# schematic.net
KiCad netlist of a schematic drawn in EAGLE
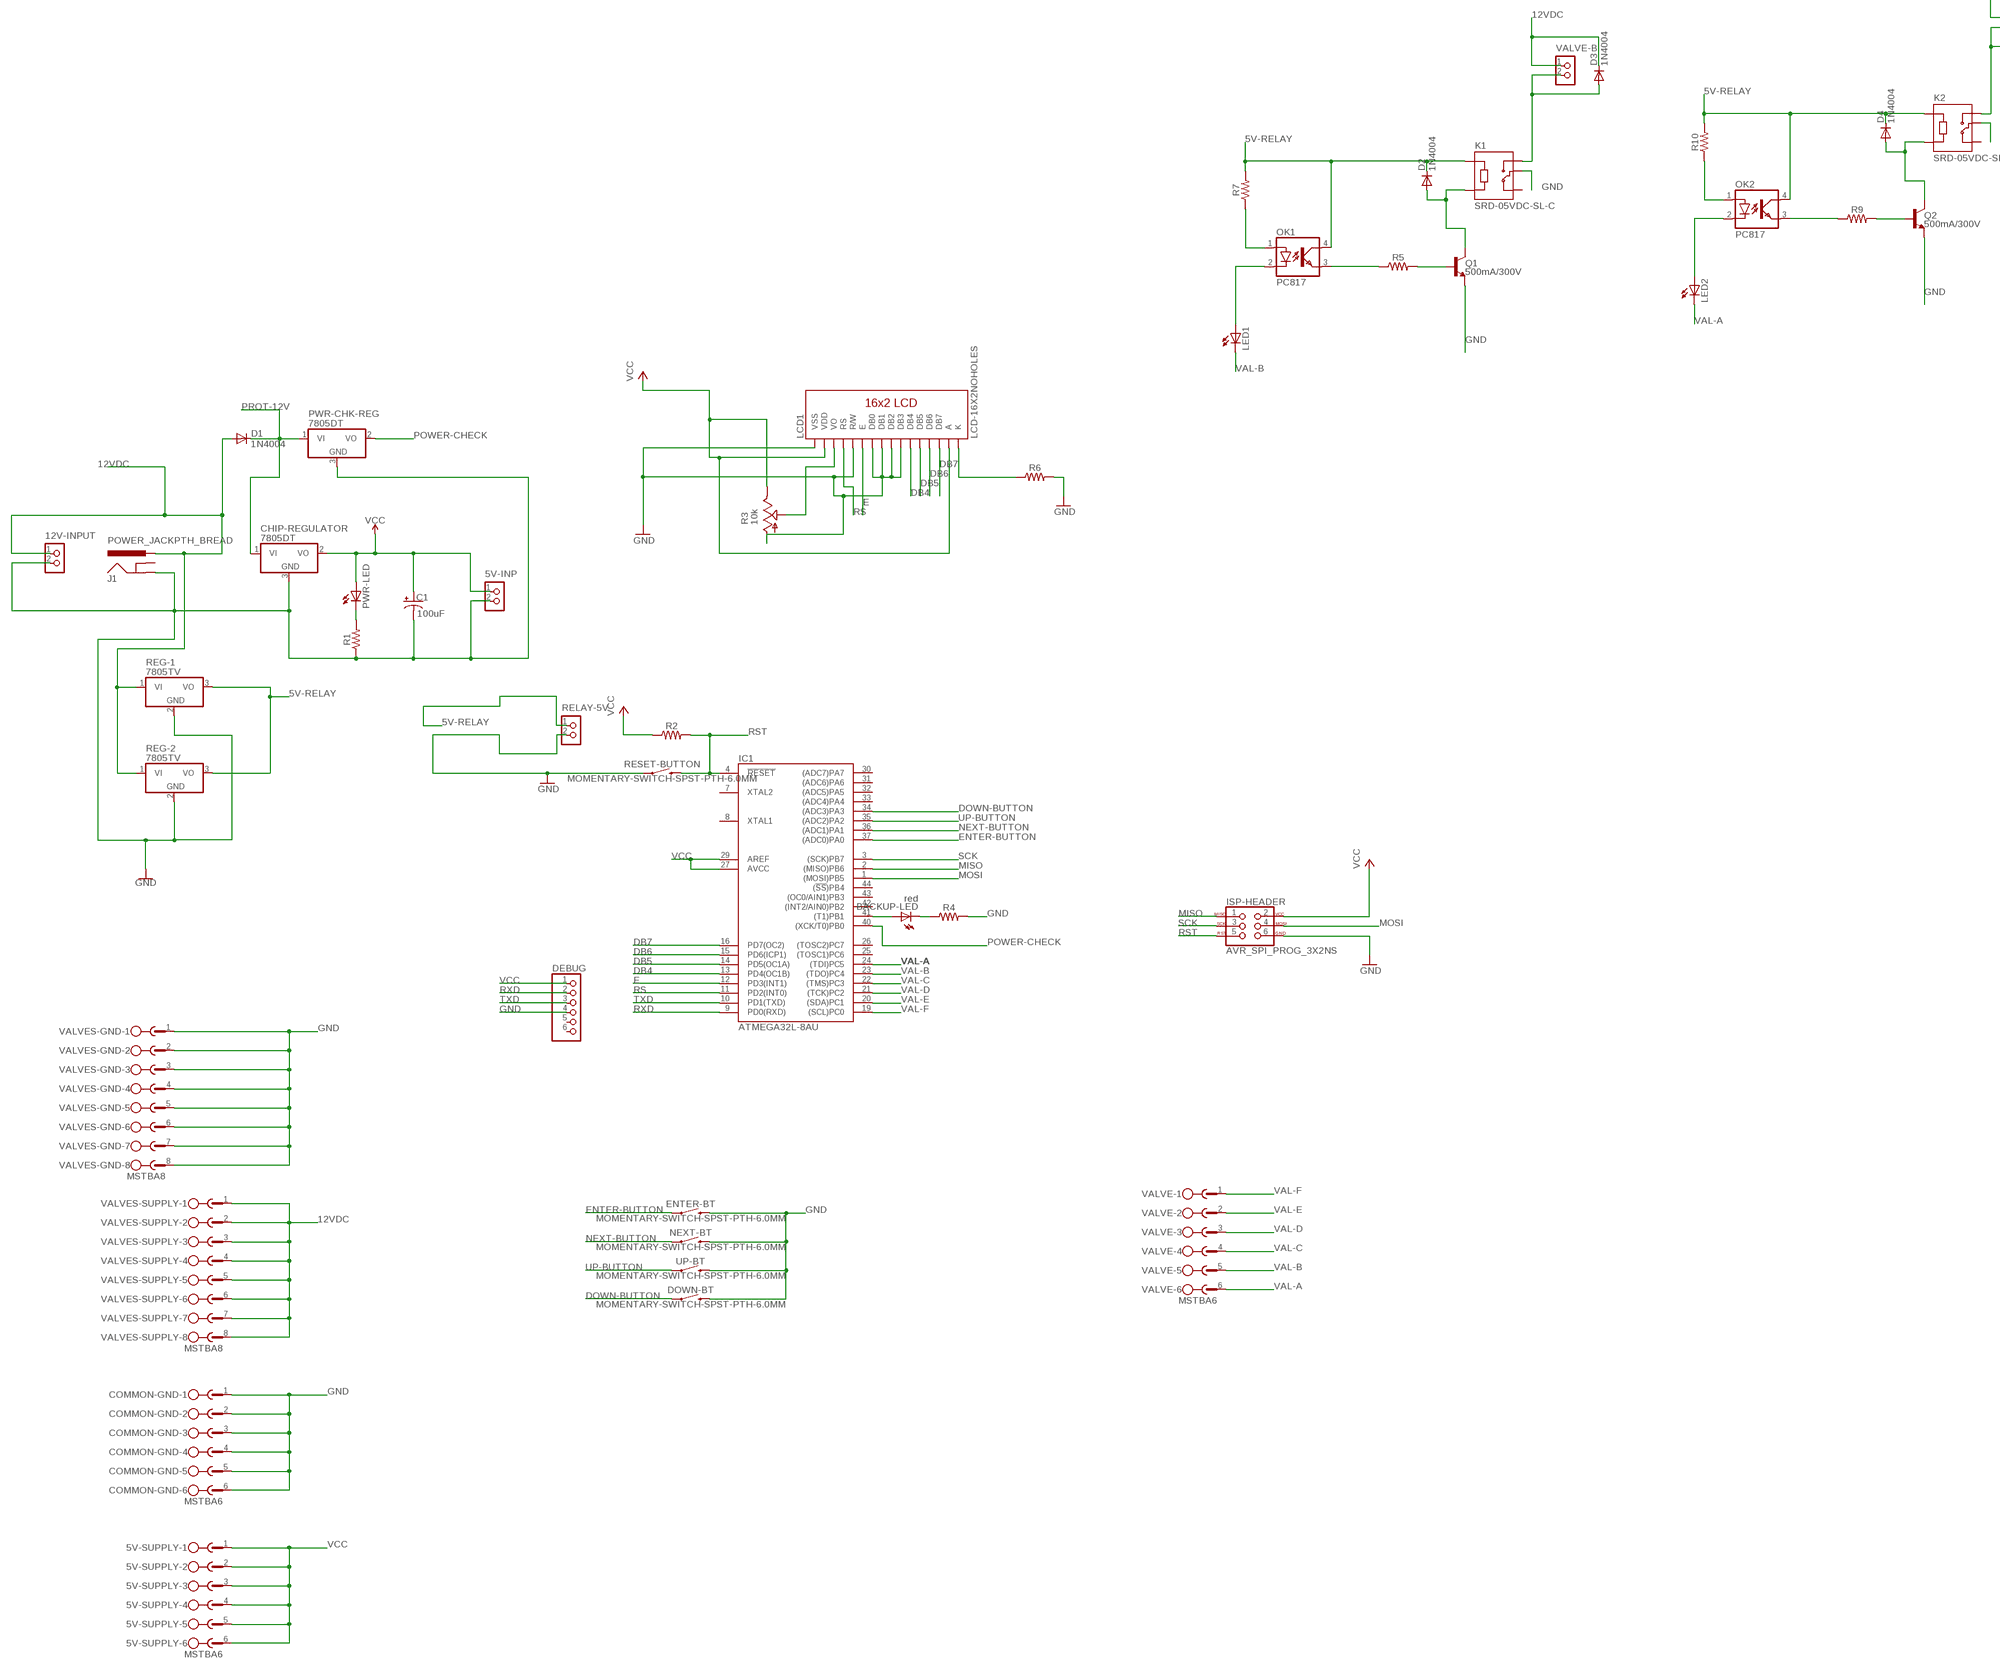
[diagram p0: schematic, sheet 1, part 1 of 2]
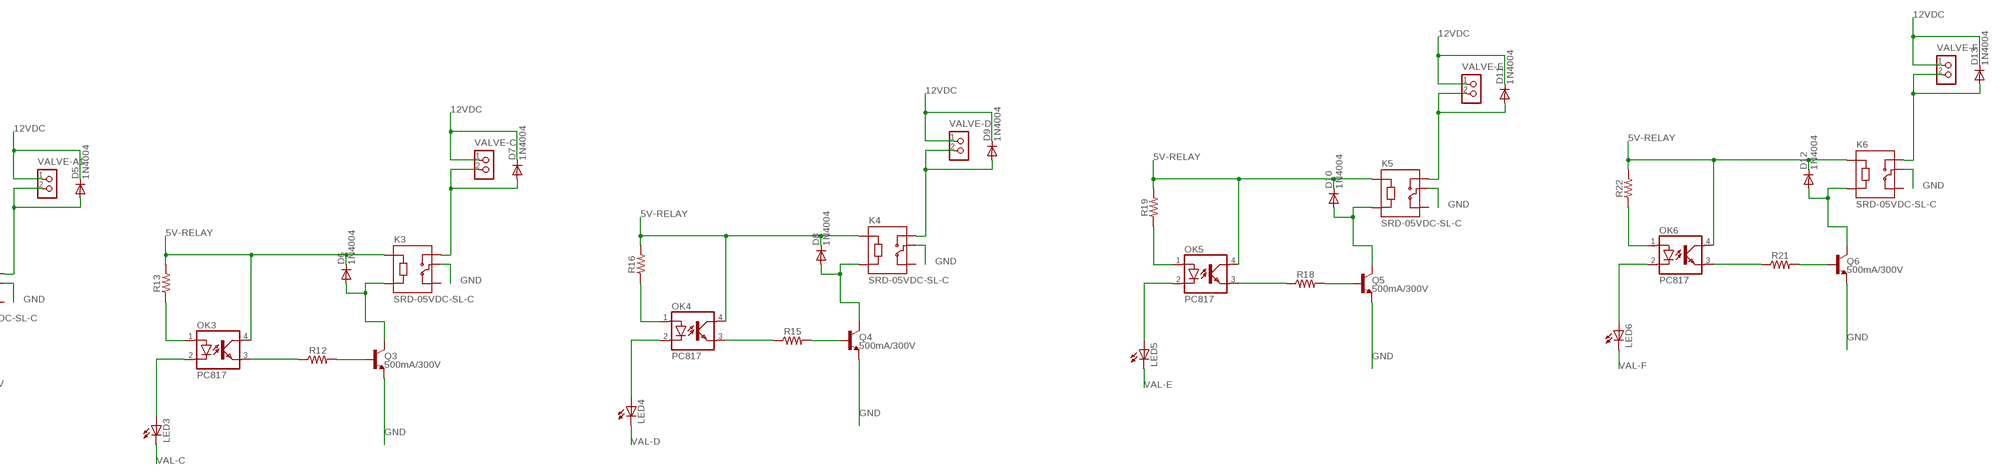
[diagram p1: schematic, sheet 1, part 2 of 2]

(export (version "E")
  (design (tool "Eeschema 10.0.6"))
  (components
    (comp (ref "5V-INP")
      (value "CON_TERMINAL_BLOCK_02-5MM")
      (footprint "eagle-import:TERMINAL_BLOCK_2P_5")
      (libsource (lib "eagle-import") (part "CON_TERMINAL_BLOCK_02-5MM"))
    )
    (comp (ref "5V-SUPPLY")
      (value "MSTBA6")
      (footprint "eagle-import:MSTBA6")
      (fields (field (name "MF") "FARNELL") (field (name "MPN") "1757284"))
      (libsource (lib "eagle-import") (part "MSTBA6"))
    )
    (comp (ref "12V-INPUT")
      (value "CON_TERMINAL_BLOCK_02-5MM")
      (footprint "eagle-import:TERMINAL_BLOCK_2P_5")
      (libsource (lib "eagle-import") (part "CON_TERMINAL_BLOCK_02-5MM"))
    )
    (comp (ref "BACKUP-LED")
      (value "red")
      (footprint "eagle-import:LED-1206")
      (libsource (lib "eagle-import") (part "LED1206"))
    )
    (comp (ref "C1")
      (value "100uF")
      (footprint "eagle-import:CPOL-RADIAL-2.5MM-6.5MM")
      (libsource (lib "eagle-import") (part "100UF-POLAR-RADIAL-2.5MM-25V-20%"))
    )
    (comp (ref "CHIP-REGULATOR")
      (value "7805DT")
      (footprint "eagle-import:TO252")
      (libsource (lib "eagle-import") (part "linear_262_78DT05"))
    )
    (comp (ref "COMMON-GND")
      (value "MSTBA6")
      (footprint "eagle-import:MSTBA6")
      (fields (field (name "MF") "FARNELL") (field (name "MPN") "1757284"))
      (libsource (lib "eagle-import") (part "MSTBA6"))
    )
    (comp (ref "D1")
      (value "1N4004")
      (footprint "eagle-import:DO41-10")
      (libsource (lib "eagle-import") (part "1N4004"))
    )
    (comp (ref "D2")
      (value "1N4004")
      (footprint "eagle-import:DO41-10")
      (libsource (lib "eagle-import") (part "1N4004"))
    )
    (comp (ref "D3")
      (value "1N4004")
      (footprint "eagle-import:DO41-10")
      (libsource (lib "eagle-import") (part "1N4004"))
    )
    (comp (ref "D4")
      (value "1N4004")
      (footprint "eagle-import:DO41-10")
      (libsource (lib "eagle-import") (part "1N4004"))
    )
    (comp (ref "D5")
      (value "1N4004")
      (footprint "eagle-import:DO41-10")
      (libsource (lib "eagle-import") (part "1N4004"))
    )
    (comp (ref "D6")
      (value "1N4004")
      (footprint "eagle-import:DO41-10")
      (libsource (lib "eagle-import") (part "1N4004"))
    )
    (comp (ref "D7")
      (value "1N4004")
      (footprint "eagle-import:DO41-10")
      (libsource (lib "eagle-import") (part "1N4004"))
    )
    (comp (ref "D8")
      (value "1N4004")
      (footprint "eagle-import:DO41-10")
      (libsource (lib "eagle-import") (part "1N4004"))
    )
    (comp (ref "D9")
      (value "1N4004")
      (footprint "eagle-import:DO41-10")
      (libsource (lib "eagle-import") (part "1N4004"))
    )
    (comp (ref "D10")
      (value "1N4004")
      (footprint "eagle-import:DO41-10")
      (libsource (lib "eagle-import") (part "1N4004"))
    )
    (comp (ref "D11")
      (value "1N4004")
      (footprint "eagle-import:DO41-10")
      (libsource (lib "eagle-import") (part "1N4004"))
    )
    (comp (ref "D12")
      (value "1N4004")
      (footprint "eagle-import:DO41-10")
      (libsource (lib "eagle-import") (part "1N4004"))
    )
    (comp (ref "D13")
      (value "1N4004")
      (footprint "eagle-import:DO41-10")
      (libsource (lib "eagle-import") (part "1N4004"))
    )
    (comp (ref "DEBUG")
      (value "PINHD-1X6B")
      (footprint "eagle-import:1X06-BIG")
      (libsource (lib "eagle-import") (part "PINHD-1X6B"))
    )
    (comp (ref "DOWN-BT")
      (value "MOMENTARY-SWITCH-SPST-PTH-6.0MM")
      (footprint "eagle-import:TACTILE_SWITCH_PTH_6.0MM")
      (libsource (lib "eagle-import") (part "MOMENTARY-SWITCH-SPST-PTH-6.0MM"))
    )
    (comp (ref "ENTER-BT")
      (value "MOMENTARY-SWITCH-SPST-PTH-6.0MM")
      (footprint "eagle-import:TACTILE_SWITCH_PTH_6.0MM")
      (libsource (lib "eagle-import") (part "MOMENTARY-SWITCH-SPST-PTH-6.0MM"))
    )
    (comp (ref "IC1")
      (value "ATMEGA32L-8AU")
      (footprint "eagle-import:QFP44_10X10_0.80")
      (libsource (lib "eagle-import") (part "ATMEGA32AUL-8"))
    )
    (comp (ref "ISP-HEADER")
      (value "AVR_SPI_PROG_3X2NS")
      (footprint "eagle-import:2X3-NS")
      (libsource (lib "eagle-import") (part "AVR_SPI_PROG_3X2NS"))
    )
    (comp (ref "J1")
      (value "POWER_JACKPTH_BREAD")
      (footprint "eagle-import:POWER_JACK_PTH_BREAD")
      (libsource (lib "eagle-import") (part "POWER_JACKPTH_BREAD"))
    )
    (comp (ref "K1")
      (value "SRD-05VDC-SL-C")
      (footprint "eagle-import:RELAY_SRD-05VDC-SL-C")
      (fields (field (name "MF") "Songle Relay"))
      (libsource (lib "eagle-import") (part "SRD-05VDC-SL-C"))
    )
    (comp (ref "K2")
      (value "SRD-05VDC-SL-C")
      (footprint "eagle-import:RELAY_SRD-05VDC-SL-C")
      (fields (field (name "MF") "Songle Relay"))
      (libsource (lib "eagle-import") (part "SRD-05VDC-SL-C"))
    )
    (comp (ref "K3")
      (value "SRD-05VDC-SL-C")
      (footprint "eagle-import:RELAY_SRD-05VDC-SL-C")
      (fields (field (name "MF") "Songle Relay"))
      (libsource (lib "eagle-import") (part "SRD-05VDC-SL-C"))
    )
    (comp (ref "K4")
      (value "SRD-05VDC-SL-C")
      (footprint "eagle-import:RELAY_SRD-05VDC-SL-C")
      (fields (field (name "MF") "Songle Relay"))
      (libsource (lib "eagle-import") (part "SRD-05VDC-SL-C"))
    )
    (comp (ref "K5")
      (value "SRD-05VDC-SL-C")
      (footprint "eagle-import:RELAY_SRD-05VDC-SL-C")
      (fields (field (name "MF") "Songle Relay"))
      (libsource (lib "eagle-import") (part "SRD-05VDC-SL-C"))
    )
    (comp (ref "K6")
      (value "SRD-05VDC-SL-C")
      (footprint "eagle-import:RELAY_SRD-05VDC-SL-C")
      (fields (field (name "MF") "Songle Relay") (field (name "SPICEPREFIX") "X"))
      (libsource (lib "eagle-import") (part "SRD-05VDC-SL-C"))
    )
    (comp (ref "LCD1")
      (value "LCD-16X2NOHOLES")
      (footprint "eagle-import:LCD-16X2_NOHOLESNOSILK")
      (libsource (lib "eagle-import") (part "LCD-16X2NOHOLES"))
    )
    (comp (ref "LED1")
      (value "LED1206")
      (footprint "eagle-import:LED-1206")
      (libsource (lib "eagle-import") (part "LED1206"))
    )
    (comp (ref "LED2")
      (value "LED1206")
      (footprint "eagle-import:LED-1206")
      (libsource (lib "eagle-import") (part "LED1206"))
    )
    (comp (ref "LED3")
      (value "LED1206")
      (footprint "eagle-import:LED-1206")
      (libsource (lib "eagle-import") (part "LED1206"))
    )
    (comp (ref "LED4")
      (value "LED1206")
      (footprint "eagle-import:LED-1206")
      (libsource (lib "eagle-import") (part "LED1206"))
    )
    (comp (ref "LED5")
      (value "LED1206")
      (footprint "eagle-import:LED-1206")
      (libsource (lib "eagle-import") (part "LED1206"))
    )
    (comp (ref "LED6")
      (value "LED1206")
      (footprint "eagle-import:LED-1206")
      (libsource (lib "eagle-import") (part "LED1206"))
    )
    (comp (ref "NEXT-BT")
      (value "MOMENTARY-SWITCH-SPST-PTH-6.0MM")
      (footprint "eagle-import:TACTILE_SWITCH_PTH_6.0MM")
      (libsource (lib "eagle-import") (part "MOMENTARY-SWITCH-SPST-PTH-6.0MM"))
    )
    (comp (ref "OK1")
      (value "PC817")
      (footprint "eagle-import:DIL04")
      (fields (field (name "MPN") "PC817X4J000F"))
      (libsource (lib "eagle-import") (part "PC817"))
    )
    (comp (ref "OK2")
      (value "PC817")
      (footprint "eagle-import:DIL04")
      (fields (field (name "MPN") "PC817X4J000F") (field (name "SPICEPREFIX") "O"))
      (libsource (lib "eagle-import") (part "PC817"))
    )
    (comp (ref "OK3")
      (value "PC817")
      (footprint "eagle-import:DIL04")
      (fields (field (name "MPN") "PC817X4J000F"))
      (libsource (lib "eagle-import") (part "PC817"))
    )
    (comp (ref "OK4")
      (value "PC817")
      (footprint "eagle-import:DIL04")
      (fields (field (name "MPN") "PC817X4J000F"))
      (libsource (lib "eagle-import") (part "PC817"))
    )
    (comp (ref "OK5")
      (value "PC817")
      (footprint "eagle-import:DIL04")
      (fields (field (name "MPN") "PC817X4J000F"))
      (libsource (lib "eagle-import") (part "PC817"))
    )
    (comp (ref "OK6")
      (value "PC817")
      (footprint "eagle-import:DIL04")
      (fields (field (name "MPN") "PC817X4J000F"))
      (libsource (lib "eagle-import") (part "PC817"))
    )
    (comp (ref "PWR-CHK-REG")
      (value "7805DT")
      (footprint "eagle-import:TO252")
      (libsource (lib "eagle-import") (part "78DT05"))
    )
    (comp (ref "PWR-LED")
      (value "LED1206")
      (footprint "eagle-import:LED-1206")
      (libsource (lib "eagle-import") (part "LED1206"))
    )
    (comp (ref "Q1")
      (value "500mA/300V")
      (footprint "eagle-import:SOT23-3")
      (libsource (lib "eagle-import") (part "TRANS_NPN-MMBTA42"))
    )
    (comp (ref "Q2")
      (value "500mA/300V")
      (footprint "eagle-import:SOT23-3")
      (libsource (lib "eagle-import") (part "TRANS_NPN-MMBTA42"))
    )
    (comp (ref "Q3")
      (value "500mA/300V")
      (footprint "eagle-import:SOT23-3")
      (libsource (lib "eagle-import") (part "TRANS_NPN-MMBTA42"))
    )
    (comp (ref "Q4")
      (value "500mA/300V")
      (footprint "eagle-import:SOT23-3")
      (libsource (lib "eagle-import") (part "TRANS_NPN-MMBTA42"))
    )
    (comp (ref "Q5")
      (value "500mA/300V")
      (footprint "eagle-import:SOT23-3")
      (libsource (lib "eagle-import") (part "TRANS_NPN-MMBTA42"))
    )
    (comp (ref "Q6")
      (value "500mA/300V")
      (footprint "eagle-import:SOT23-3")
      (libsource (lib "eagle-import") (part "TRANS_NPN-MMBTA42"))
    )
    (comp (ref "R1")
      (value "RESISTOR1206")
      (footprint "eagle-import:1206")
      (fields (field (name "PROD_ID") " 330ohms"))
      (libsource (lib "eagle-import") (part "RESISTOR1206"))
    )
    (comp (ref "R2")
      (value "RESISTOR1206")
      (footprint "eagle-import:1206")
      (libsource (lib "eagle-import") (part "RESISTOR1206"))
    )
    (comp (ref "R3")
      (value "10k")
      (footprint "eagle-import:CA6V")
      (libsource (lib "eagle-import") (part "TRIM_US-CA6V"))
    )
    (comp (ref "R4")
      (value "RESISTOR1206")
      (footprint "eagle-import:1206")
      (libsource (lib "eagle-import") (part "RESISTOR1206"))
    )
    (comp (ref "R5")
      (value "RESISTOR1206")
      (footprint "eagle-import:1206")
      (libsource (lib "eagle-import") (part "RESISTOR1206"))
    )
    (comp (ref "R6")
      (value "RESISTOR1206")
      (footprint "eagle-import:1206")
      (libsource (lib "eagle-import") (part "RESISTOR1206"))
    )
    (comp (ref "R7")
      (value "RESISTOR1206")
      (footprint "eagle-import:1206")
      (libsource (lib "eagle-import") (part "RESISTOR1206"))
    )
    (comp (ref "R9")
      (value "RESISTOR1206")
      (footprint "eagle-import:1206")
      (libsource (lib "eagle-import") (part "RESISTOR1206"))
    )
    (comp (ref "R10")
      (value "RESISTOR1206")
      (footprint "eagle-import:1206")
      (libsource (lib "eagle-import") (part "RESISTOR1206"))
    )
    (comp (ref "R12")
      (value "RESISTOR1206")
      (footprint "eagle-import:1206")
      (libsource (lib "eagle-import") (part "RESISTOR1206"))
    )
    (comp (ref "R13")
      (value "RESISTOR1206")
      (footprint "eagle-import:1206")
      (libsource (lib "eagle-import") (part "RESISTOR1206"))
    )
    (comp (ref "R15")
      (value "RESISTOR1206")
      (footprint "eagle-import:1206")
      (libsource (lib "eagle-import") (part "RESISTOR1206"))
    )
    (comp (ref "R16")
      (value "RESISTOR1206")
      (footprint "eagle-import:1206")
      (libsource (lib "eagle-import") (part "RESISTOR1206"))
    )
    (comp (ref "R18")
      (value "RESISTOR1206")
      (footprint "eagle-import:1206")
      (libsource (lib "eagle-import") (part "RESISTOR1206"))
    )
    (comp (ref "R19")
      (value "RESISTOR1206")
      (footprint "eagle-import:1206")
      (libsource (lib "eagle-import") (part "RESISTOR1206"))
    )
    (comp (ref "R21")
      (value "RESISTOR1206")
      (footprint "eagle-import:1206")
      (libsource (lib "eagle-import") (part "RESISTOR1206"))
    )
    (comp (ref "R22")
      (value "RESISTOR1206")
      (footprint "eagle-import:1206")
      (libsource (lib "eagle-import") (part "RESISTOR1206"))
    )
    (comp (ref "REG-1")
      (value "7805TV")
      (footprint "eagle-import:TO220V")
      (libsource (lib "eagle-import") (part "78TV05"))
    )
    (comp (ref "REG-2")
      (value "7805TV")
      (footprint "eagle-import:TO220V")
      (libsource (lib "eagle-import") (part "78TV05"))
    )
    (comp (ref "RELAY-5V")
      (value "CON_TERMINAL_BLOCK_02-5MM")
      (footprint "eagle-import:TERMINAL_BLOCK_2P_5")
      (libsource (lib "eagle-import") (part "CON_TERMINAL_BLOCK_02-5MM"))
    )
    (comp (ref "RESET-BUTTON")
      (value "MOMENTARY-SWITCH-SPST-PTH-6.0MM")
      (footprint "eagle-import:TACTILE_SWITCH_PTH_6.0MM")
      (libsource (lib "eagle-import") (part "MOMENTARY-SWITCH-SPST-PTH-6.0MM"))
    )
    (comp (ref "UP-BT")
      (value "MOMENTARY-SWITCH-SPST-PTH-6.0MM")
      (footprint "eagle-import:TACTILE_SWITCH_PTH_6.0MM")
      (libsource (lib "eagle-import") (part "MOMENTARY-SWITCH-SPST-PTH-6.0MM"))
    )
    (comp (ref "VALVE")
      (value "MSTBA6")
      (footprint "eagle-import:MSTBA6")
      (fields (field (name "MF") "FARNELL") (field (name "MPN") "1757284"))
      (libsource (lib "eagle-import") (part "MSTBA6"))
    )
    (comp (ref "VALVE-A1")
      (value "CON_TERMINAL_BLOCK_02-5MM")
      (footprint "eagle-import:TERMINAL_BLOCK_2P_5")
      (libsource (lib "eagle-import") (part "CON_TERMINAL_BLOCK_02-5MM"))
    )
    (comp (ref "VALVE-B")
      (value "CON_TERMINAL_BLOCK_02-5MM")
      (footprint "eagle-import:TERMINAL_BLOCK_2P_5")
      (libsource (lib "eagle-import") (part "CON_TERMINAL_BLOCK_02-5MM"))
    )
    (comp (ref "VALVE-C")
      (value "CON_TERMINAL_BLOCK_02-5MM")
      (footprint "eagle-import:TERMINAL_BLOCK_2P_5")
      (libsource (lib "eagle-import") (part "CON_TERMINAL_BLOCK_02-5MM"))
    )
    (comp (ref "VALVE-D")
      (value "CON_TERMINAL_BLOCK_02-5MM")
      (footprint "eagle-import:TERMINAL_BLOCK_2P_5")
      (libsource (lib "eagle-import") (part "CON_TERMINAL_BLOCK_02-5MM"))
    )
    (comp (ref "VALVE-E")
      (value "CON_TERMINAL_BLOCK_02-5MM")
      (footprint "eagle-import:TERMINAL_BLOCK_2P_5")
      (libsource (lib "eagle-import") (part "CON_TERMINAL_BLOCK_02-5MM"))
    )
    (comp (ref "VALVE-F")
      (value "CON_TERMINAL_BLOCK_02-5MM")
      (footprint "eagle-import:TERMINAL_BLOCK_2P_5")
      (libsource (lib "eagle-import") (part "CON_TERMINAL_BLOCK_02-5MM"))
    )
    (comp (ref "VALVES-GND")
      (value "MSTBA8")
      (footprint "eagle-import:MSTBA8")
      (fields (field (name "MF") "FARNELL") (field (name "MPN") "1757307"))
      (libsource (lib "eagle-import") (part "MSTBA8"))
    )
    (comp (ref "VALVES-SUPPLY")
      (value "MSTBA8")
      (footprint "eagle-import:MSTBA8")
      (fields (field (name "MF") "FARNELL") (field (name "MPN") "1757307") (field (name "SPICEPREFIX") "X"))
      (libsource (lib "eagle-import") (part "MSTBA8"))
    )
  )
  (nets
    (net (code "1") (name "/5V-RELAY") (class "Default")
      (node (ref "D10") (pin "C") (pinfunction "C_C") (pintype "passive"))
      (node (ref "D12") (pin "C") (pinfunction "C_C") (pintype "passive"))
      (node (ref "D2") (pin "C") (pinfunction "C_C") (pintype "passive"))
      (node (ref "D4") (pin "C") (pinfunction "C_C") (pintype "passive"))
      (node (ref "D6") (pin "C") (pinfunction "C_C") (pintype "passive"))
      (node (ref "D8") (pin "C") (pinfunction "C_C") (pintype "passive"))
      (node (ref "K1") (pin "A1") (pinfunction "A1_A1") (pintype "passive"))
      (node (ref "K2") (pin "A1") (pinfunction "A1_A1") (pintype "passive"))
      (node (ref "K3") (pin "A1") (pinfunction "A1_A1") (pintype "passive"))
      (node (ref "K4") (pin "A1") (pinfunction "A1_A1") (pintype "passive"))
      (node (ref "K5") (pin "A1") (pinfunction "A1_A1") (pintype "passive"))
      (node (ref "K6") (pin "A1") (pinfunction "A1_A1") (pintype "passive"))
      (node (ref "OK1") (pin "4") (pinfunction "COL_4") (pintype "passive"))
      (node (ref "OK2") (pin "4") (pinfunction "COL_4") (pintype "passive"))
      (node (ref "OK3") (pin "4") (pinfunction "COL_4") (pintype "passive"))
      (node (ref "OK4") (pin "4") (pinfunction "COL_4") (pintype "passive"))
      (node (ref "OK5") (pin "4") (pinfunction "COL_4") (pintype "passive"))
      (node (ref "OK6") (pin "4") (pinfunction "COL_4") (pintype "passive"))
      (node (ref "R10") (pin "2") (pinfunction "2_2") (pintype "passive"))
      (node (ref "R13") (pin "2") (pinfunction "2_2") (pintype "passive"))
      (node (ref "R16") (pin "2") (pinfunction "2_2") (pintype "passive"))
      (node (ref "R19") (pin "2") (pinfunction "2_2") (pintype "passive"))
      (node (ref "R22") (pin "2") (pinfunction "2_2") (pintype "passive"))
      (node (ref "R7") (pin "2") (pinfunction "2_2") (pintype "passive"))
      (node (ref "REG-1") (pin "3") (pinfunction "VO_3") (pintype "passive"))
      (node (ref "REG-2") (pin "3") (pinfunction "VO_3") (pintype "passive"))
      (node (ref "RELAY-5V") (pin "1") (pinfunction "1_1") (pintype "passive"))
    )
    (net (code "2") (name "/12VDC") (class "Default")
      (node (ref "12V-INPUT") (pin "1") (pinfunction "1_1") (pintype "passive"))
      (node (ref "D1") (pin "A") (pinfunction "A_A") (pintype "passive"))
      (node (ref "D11") (pin "C") (pinfunction "C_C") (pintype "passive"))
      (node (ref "D13") (pin "C") (pinfunction "C_C") (pintype "passive"))
      (node (ref "D3") (pin "C") (pinfunction "C_C") (pintype "passive"))
      (node (ref "D5") (pin "C") (pinfunction "C_C") (pintype "passive"))
      (node (ref "D7") (pin "C") (pinfunction "C_C") (pintype "passive"))
      (node (ref "D9") (pin "C") (pinfunction "C_C") (pintype "passive"))
      (node (ref "J1") (pin "PWR") (pinfunction "PWR_PWR") (pintype "bidirectional"))
      (node (ref "REG-1") (pin "1") (pinfunction "VI_1") (pintype "input"))
      (node (ref "REG-2") (pin "1") (pinfunction "VI_1") (pintype "input"))
      (node (ref "VALVE-A1") (pin "1") (pinfunction "1_1") (pintype "passive"))
      (node (ref "VALVE-B") (pin "1") (pinfunction "1_1") (pintype "passive"))
      (node (ref "VALVE-C") (pin "1") (pinfunction "1_1") (pintype "passive"))
      (node (ref "VALVE-D") (pin "1") (pinfunction "1_1") (pintype "passive"))
      (node (ref "VALVE-E") (pin "1") (pinfunction "1_1") (pintype "passive"))
      (node (ref "VALVE-F") (pin "1") (pinfunction "1_1") (pintype "passive"))
      (node (ref "VALVES-SUPPLY") (pin "1") (pinfunction "1_1") (pintype "passive"))
      (node (ref "VALVES-SUPPLY") (pin "2") (pinfunction "1_2") (pintype "passive"))
      (node (ref "VALVES-SUPPLY") (pin "3") (pinfunction "1_3") (pintype "passive"))
      (node (ref "VALVES-SUPPLY") (pin "4") (pinfunction "1_4") (pintype "passive"))
      (node (ref "VALVES-SUPPLY") (pin "5") (pinfunction "1_5") (pintype "passive"))
      (node (ref "VALVES-SUPPLY") (pin "6") (pinfunction "1_6") (pintype "passive"))
      (node (ref "VALVES-SUPPLY") (pin "7") (pinfunction "1_7") (pintype "passive"))
      (node (ref "VALVES-SUPPLY") (pin "8") (pinfunction "1_8") (pintype "passive"))
    )
    (net (code "3") (name "/DB4") (class "Default")
      (node (ref "IC1") (pin "13") (pinfunction "PD4(OC1B)_13") (pintype "bidirectional"))
      (node (ref "LCD1") (pin "11") (pinfunction "DB4_11") (pintype "bidirectional"))
    )
    (net (code "4") (name "/DB5") (class "Default")
      (node (ref "IC1") (pin "14") (pinfunction "PD5(OC1A)_14") (pintype "bidirectional"))
      (node (ref "LCD1") (pin "12") (pinfunction "DB5_12") (pintype "bidirectional"))
    )
    (net (code "5") (name "/DB6") (class "Default")
      (node (ref "IC1") (pin "15") (pinfunction "PD6(ICP1)_15") (pintype "bidirectional"))
      (node (ref "LCD1") (pin "13") (pinfunction "DB6_13") (pintype "bidirectional"))
    )
    (net (code "6") (name "/DB7") (class "Default")
      (node (ref "IC1") (pin "16") (pinfunction "PD7(OC2)_16") (pintype "bidirectional"))
      (node (ref "LCD1") (pin "14") (pinfunction "DB7_14") (pintype "bidirectional"))
    )
    (net (code "7") (name "/DOWN-BUTTON") (class "Default")
      (node (ref "DOWN-BT") (pin "1") (pinfunction "1_1") (pintype "passive"))
      (node (ref "IC1") (pin "34") (pinfunction "(ADC3)PA3_34") (pintype "bidirectional"))
    )
    (net (code "8") (name "/E") (class "Default")
      (node (ref "IC1") (pin "12") (pinfunction "PD3(INT1)_12") (pintype "bidirectional"))
      (node (ref "LCD1") (pin "6") (pinfunction "E_6") (pintype "input"))
    )
    (net (code "9") (name "/ENTER-BUTTON") (class "Default")
      (node (ref "ENTER-BT") (pin "1") (pinfunction "1_1") (pintype "passive"))
      (node (ref "IC1") (pin "37") (pinfunction "(ADC0)PA0_37") (pintype "bidirectional"))
    )
    (net (code "10") (name "/MISO") (class "Default")
      (node (ref "IC1") (pin "2") (pinfunction "(MISO)PB6_2") (pintype "bidirectional"))
      (node (ref "ISP-HEADER") (pin "1") (pinfunction "1_1") (pintype "passive"))
    )
    (net (code "11") (name "/MOSI") (class "Default")
      (node (ref "IC1") (pin "1") (pinfunction "(MOSI)PB5_1") (pintype "bidirectional"))
      (node (ref "ISP-HEADER") (pin "4") (pinfunction "4_4") (pintype "passive"))
    )
    (net (code "12") (name "/NEXT-BUTTON") (class "Default")
      (node (ref "IC1") (pin "36") (pinfunction "(ADC1)PA1_36") (pintype "bidirectional"))
      (node (ref "NEXT-BT") (pin "1") (pinfunction "1_1") (pintype "passive"))
    )
    (net (code "13") (name "/POWER-CHECK") (class "Default")
      (node (ref "IC1") (pin "40") (pinfunction "(XCK/T0)PB0_40") (pintype "bidirectional"))
      (node (ref "PWR-CHK-REG") (pin "2") (pinfunction "VO_2") (pintype "passive"))
    )
    (net (code "14") (name "/PROT-12V") (class "Default")
      (node (ref "CHIP-REGULATOR") (pin "1") (pinfunction "VI_1") (pintype "input"))
      (node (ref "D1") (pin "C") (pinfunction "C_C") (pintype "passive"))
      (node (ref "PWR-CHK-REG") (pin "1") (pinfunction "VI_1") (pintype "input"))
    )
    (net (code "15") (name "/RS") (class "Default")
      (node (ref "IC1") (pin "11") (pinfunction "PD2(INT0)_11") (pintype "bidirectional"))
      (node (ref "LCD1") (pin "4") (pinfunction "RS_4") (pintype "input"))
    )
    (net (code "16") (name "/RST") (class "Default")
      (node (ref "IC1") (pin "4") (pinfunction "~{RESET}_4") (pintype "input"))
      (node (ref "ISP-HEADER") (pin "5") (pinfunction "5_5") (pintype "passive"))
      (node (ref "R2") (pin "2") (pinfunction "2_2") (pintype "passive"))
      (node (ref "RESET-BUTTON") (pin "3") (pinfunction "2_3") (pintype "passive"))
    )
    (net (code "17") (name "/RXD") (class "Default")
      (node (ref "DEBUG") (pin "2") (pinfunction "2_2") (pintype "passive"))
      (node (ref "IC1") (pin "9") (pinfunction "PD0(RXD)_9") (pintype "bidirectional"))
    )
    (net (code "18") (name "/SCK") (class "Default")
      (node (ref "IC1") (pin "3") (pinfunction "(SCK)PB7_3") (pintype "bidirectional"))
      (node (ref "ISP-HEADER") (pin "3") (pinfunction "3_3") (pintype "passive"))
    )
    (net (code "19") (name "/TXD") (class "Default")
      (node (ref "DEBUG") (pin "3") (pinfunction "3_3") (pintype "passive"))
      (node (ref "IC1") (pin "10") (pinfunction "PD1(TXD)_10") (pintype "bidirectional"))
    )
    (net (code "20") (name "/UP-BUTTON") (class "Default")
      (node (ref "IC1") (pin "35") (pinfunction "(ADC2)PA2_35") (pintype "bidirectional"))
      (node (ref "UP-BT") (pin "1") (pinfunction "1_1") (pintype "passive"))
    )
    (net (code "21") (name "/VAL-A") (class "Default")
      (node (ref "IC1") (pin "24") (pinfunction "(TDI)PC5_24") (pintype "bidirectional"))
      (node (ref "LED2") (pin "C") (pinfunction "C_C") (pintype "passive"))
      (node (ref "VALVE") (pin "6") (pinfunction "1_6") (pintype "passive"))
    )
    (net (code "22") (name "/VAL-B") (class "Default")
      (node (ref "IC1") (pin "23") (pinfunction "(TDO)PC4_23") (pintype "bidirectional"))
      (node (ref "LED1") (pin "C") (pinfunction "C_C") (pintype "passive"))
      (node (ref "VALVE") (pin "5") (pinfunction "1_5") (pintype "passive"))
    )
    (net (code "23") (name "/VAL-C") (class "Default")
      (node (ref "IC1") (pin "22") (pinfunction "(TMS)PC3_22") (pintype "bidirectional"))
      (node (ref "LED3") (pin "C") (pinfunction "C_C") (pintype "passive"))
      (node (ref "VALVE") (pin "4") (pinfunction "1_4") (pintype "passive"))
    )
    (net (code "24") (name "/VAL-D") (class "Default")
      (node (ref "IC1") (pin "21") (pinfunction "(TCK)PC2_21") (pintype "bidirectional"))
      (node (ref "LED4") (pin "C") (pinfunction "C_C") (pintype "passive"))
      (node (ref "VALVE") (pin "3") (pinfunction "1_3") (pintype "passive"))
    )
    (net (code "25") (name "/VAL-E") (class "Default")
      (node (ref "IC1") (pin "20") (pinfunction "(SDA)PC1_20") (pintype "bidirectional"))
      (node (ref "LED5") (pin "C") (pinfunction "C_C") (pintype "passive"))
      (node (ref "VALVE") (pin "2") (pinfunction "1_2") (pintype "passive"))
    )
    (net (code "26") (name "/VAL-F") (class "Default")
      (node (ref "IC1") (pin "19") (pinfunction "(SCL)PC0_19") (pintype "bidirectional"))
      (node (ref "LED6") (pin "C") (pinfunction "C_C") (pintype "passive"))
      (node (ref "VALVE") (pin "1") (pinfunction "1_1") (pintype "passive"))
    )
    (net (code "27") (name "GND") (class "Default")
      (node (ref "12V-INPUT") (pin "2") (pinfunction "2_2") (pintype "passive"))
      (node (ref "5V-INP") (pin "2") (pinfunction "2_2") (pintype "passive"))
      (node (ref "C1") (pin "2") (pinfunction "-_2") (pintype "passive"))
      (node (ref "CHIP-REGULATOR") (pin "3") (pinfunction "GND_3") (pintype "passive"))
      (node (ref "COMMON-GND") (pin "1") (pinfunction "1_1") (pintype "passive"))
      (node (ref "COMMON-GND") (pin "2") (pinfunction "1_2") (pintype "passive"))
      (node (ref "COMMON-GND") (pin "3") (pinfunction "1_3") (pintype "passive"))
      (node (ref "COMMON-GND") (pin "4") (pinfunction "1_4") (pintype "passive"))
      (node (ref "COMMON-GND") (pin "5") (pinfunction "1_5") (pintype "passive"))
      (node (ref "COMMON-GND") (pin "6") (pinfunction "1_6") (pintype "passive"))
      (node (ref "DEBUG") (pin "4") (pinfunction "4_4") (pintype "passive"))
      (node (ref "DOWN-BT") (pin "3") (pinfunction "2_3") (pintype "passive"))
      (node (ref "ENTER-BT") (pin "3") (pinfunction "2_3") (pintype "passive"))
      (node (ref "ISP-HEADER") (pin "6") (pinfunction "6_6") (pintype "passive"))
      (node (ref "J1") (pin "GND") (pinfunction "GND_GND") (pintype "bidirectional"))
      (node (ref "K1") (pin "COM") (pinfunction "COM_COM") (pintype "passive"))
      (node (ref "K2") (pin "COM") (pinfunction "COM_COM") (pintype "passive"))
      (node (ref "K3") (pin "COM") (pinfunction "COM_COM") (pintype "passive"))
      (node (ref "K4") (pin "COM") (pinfunction "COM_COM") (pintype "passive"))
      (node (ref "K5") (pin "COM") (pinfunction "COM_COM") (pintype "passive"))
      (node (ref "K6") (pin "COM") (pinfunction "COM_COM") (pintype "passive"))
      (node (ref "LCD1") (pin "1") (pinfunction "VSS_1") (pintype "power_in"))
      (node (ref "LCD1") (pin "10") (pinfunction "DB3_10") (pintype "bidirectional"))
      (node (ref "LCD1") (pin "5") (pinfunction "R/W_5") (pintype "input"))
      (node (ref "LCD1") (pin "7") (pinfunction "DB0_7") (pintype "bidirectional"))
      (node (ref "LCD1") (pin "8") (pinfunction "DB1_8") (pintype "bidirectional"))
      (node (ref "LCD1") (pin "9") (pinfunction "DB2_9") (pintype "bidirectional"))
      (node (ref "NEXT-BT") (pin "3") (pinfunction "2_3") (pintype "passive"))
      (node (ref "PWR-CHK-REG") (pin "3") (pinfunction "GND_3") (pintype "passive"))
      (node (ref "Q1") (pin "2") (pinfunction "E_2") (pintype "passive"))
      (node (ref "Q2") (pin "2") (pinfunction "E_2") (pintype "passive"))
      (node (ref "Q3") (pin "2") (pinfunction "E_2") (pintype "passive"))
      (node (ref "Q4") (pin "2") (pinfunction "E_2") (pintype "passive"))
      (node (ref "Q5") (pin "2") (pinfunction "E_2") (pintype "passive"))
      (node (ref "Q6") (pin "2") (pinfunction "E_2") (pintype "passive"))
      (node (ref "R1") (pin "1") (pinfunction "1_1") (pintype "passive"))
      (node (ref "R3") (pin "A") (pinfunction "A_A") (pintype "passive"))
      (node (ref "R4") (pin "2") (pinfunction "2_2") (pintype "passive"))
      (node (ref "R6") (pin "2") (pinfunction "2_2") (pintype "passive"))
      (node (ref "REG-1") (pin "2") (pinfunction "GND_2") (pintype "passive"))
      (node (ref "REG-2") (pin "2") (pinfunction "GND_2") (pintype "passive"))
      (node (ref "RELAY-5V") (pin "2") (pinfunction "2_2") (pintype "passive"))
      (node (ref "RESET-BUTTON") (pin "1") (pinfunction "1_1") (pintype "passive"))
      (node (ref "UP-BT") (pin "3") (pinfunction "2_3") (pintype "passive"))
      (node (ref "VALVES-GND") (pin "1") (pinfunction "1_1") (pintype "passive"))
      (node (ref "VALVES-GND") (pin "2") (pinfunction "1_2") (pintype "passive"))
      (node (ref "VALVES-GND") (pin "3") (pinfunction "1_3") (pintype "passive"))
      (node (ref "VALVES-GND") (pin "4") (pinfunction "1_4") (pintype "passive"))
      (node (ref "VALVES-GND") (pin "5") (pinfunction "1_5") (pintype "passive"))
      (node (ref "VALVES-GND") (pin "6") (pinfunction "1_6") (pintype "passive"))
      (node (ref "VALVES-GND") (pin "7") (pinfunction "1_7") (pintype "passive"))
      (node (ref "VALVES-GND") (pin "8") (pinfunction "1_8") (pintype "passive"))
    )
    (net (code "28") (name "Net-(BACKUP-LED-PadC)") (class "Default")
      (node (ref "BACKUP-LED") (pin "C") (pinfunction "C_C") (pintype "passive"))
      (node (ref "R4") (pin "1") (pinfunction "1_1") (pintype "passive"))
    )
    (net (code "29") (name "Net-(D3-PadA)") (class "Default")
      (node (ref "D3") (pin "A") (pinfunction "A_A") (pintype "passive"))
      (node (ref "K1") (pin "NO") (pinfunction "NO_NO") (pintype "passive"))
      (node (ref "VALVE-B") (pin "2") (pinfunction "2_2") (pintype "passive"))
    )
    (net (code "30") (name "Net-(D5-PadA)") (class "Default")
      (node (ref "D5") (pin "A") (pinfunction "A_A") (pintype "passive"))
      (node (ref "K2") (pin "NO") (pinfunction "NO_NO") (pintype "passive"))
      (node (ref "VALVE-A1") (pin "2") (pinfunction "2_2") (pintype "passive"))
    )
    (net (code "31") (name "Net-(D7-PadA)") (class "Default")
      (node (ref "D7") (pin "A") (pinfunction "A_A") (pintype "passive"))
      (node (ref "K3") (pin "NO") (pinfunction "NO_NO") (pintype "passive"))
      (node (ref "VALVE-C") (pin "2") (pinfunction "2_2") (pintype "passive"))
    )
    (net (code "32") (name "Net-(D9-PadA)") (class "Default")
      (node (ref "D9") (pin "A") (pinfunction "A_A") (pintype "passive"))
      (node (ref "K4") (pin "NO") (pinfunction "NO_NO") (pintype "passive"))
      (node (ref "VALVE-D") (pin "2") (pinfunction "2_2") (pintype "passive"))
    )
    (net (code "33") (name "Net-(D11-PadA)") (class "Default")
      (node (ref "D11") (pin "A") (pinfunction "A_A") (pintype "passive"))
      (node (ref "K5") (pin "NO") (pinfunction "NO_NO") (pintype "passive"))
      (node (ref "VALVE-E") (pin "2") (pinfunction "2_2") (pintype "passive"))
    )
    (net (code "34") (name "Net-(D13-PadA)") (class "Default")
      (node (ref "D13") (pin "A") (pinfunction "A_A") (pintype "passive"))
      (node (ref "K6") (pin "NO") (pinfunction "NO_NO") (pintype "passive"))
      (node (ref "VALVE-F") (pin "2") (pinfunction "2_2") (pintype "passive"))
    )
    (net (code "35") (name "Net-(IC1A-(T1)PB1)") (class "Default")
      (node (ref "BACKUP-LED") (pin "A") (pinfunction "A_A") (pintype "passive"))
      (node (ref "IC1") (pin "41") (pinfunction "(T1)PB1_41") (pintype "bidirectional"))
    )
    (net (code "36") (name "Net-(LCD1-K)") (class "Default")
      (node (ref "LCD1") (pin "16") (pinfunction "K_16") (pintype "power_in"))
      (node (ref "R6") (pin "1") (pinfunction "1_1") (pintype "passive"))
    )
    (net (code "37") (name "Net-(LCD1-VO)") (class "Default")
      (node (ref "LCD1") (pin "3") (pinfunction "VO_3") (pintype "bidirectional"))
      (node (ref "R3") (pin "S") (pinfunction "S_S") (pintype "passive"))
    )
    (net (code "38") (name "Net-(OK1-A)") (class "Default")
      (node (ref "OK1") (pin "1") (pinfunction "A_1") (pintype "passive"))
      (node (ref "R7") (pin "1") (pinfunction "1_1") (pintype "passive"))
    )
    (net (code "39") (name "Net-(OK1-C)") (class "Default")
      (node (ref "LED1") (pin "A") (pinfunction "A_A") (pintype "passive"))
      (node (ref "OK1") (pin "2") (pinfunction "C_2") (pintype "passive"))
    )
    (net (code "40") (name "Net-(OK1-EMIT)") (class "Default")
      (node (ref "OK1") (pin "3") (pinfunction "EMIT_3") (pintype "passive"))
      (node (ref "R5") (pin "1") (pinfunction "1_1") (pintype "passive"))
    )
    (net (code "41") (name "Net-(OK2-A)") (class "Default")
      (node (ref "OK2") (pin "1") (pinfunction "A_1") (pintype "passive"))
      (node (ref "R10") (pin "1") (pinfunction "1_1") (pintype "passive"))
    )
    (net (code "42") (name "Net-(OK2-C)") (class "Default")
      (node (ref "LED2") (pin "A") (pinfunction "A_A") (pintype "passive"))
      (node (ref "OK2") (pin "2") (pinfunction "C_2") (pintype "passive"))
    )
    (net (code "43") (name "Net-(OK2-EMIT)") (class "Default")
      (node (ref "OK2") (pin "3") (pinfunction "EMIT_3") (pintype "passive"))
      (node (ref "R9") (pin "1") (pinfunction "1_1") (pintype "passive"))
    )
    (net (code "44") (name "Net-(OK3-A)") (class "Default")
      (node (ref "OK3") (pin "1") (pinfunction "A_1") (pintype "passive"))
      (node (ref "R13") (pin "1") (pinfunction "1_1") (pintype "passive"))
    )
    (net (code "45") (name "Net-(OK3-C)") (class "Default")
      (node (ref "LED3") (pin "A") (pinfunction "A_A") (pintype "passive"))
      (node (ref "OK3") (pin "2") (pinfunction "C_2") (pintype "passive"))
    )
    (net (code "46") (name "Net-(OK3-EMIT)") (class "Default")
      (node (ref "OK3") (pin "3") (pinfunction "EMIT_3") (pintype "passive"))
      (node (ref "R12") (pin "1") (pinfunction "1_1") (pintype "passive"))
    )
    (net (code "47") (name "Net-(OK4-A)") (class "Default")
      (node (ref "OK4") (pin "1") (pinfunction "A_1") (pintype "passive"))
      (node (ref "R16") (pin "1") (pinfunction "1_1") (pintype "passive"))
    )
    (net (code "48") (name "Net-(OK4-C)") (class "Default")
      (node (ref "LED4") (pin "A") (pinfunction "A_A") (pintype "passive"))
      (node (ref "OK4") (pin "2") (pinfunction "C_2") (pintype "passive"))
    )
    (net (code "49") (name "Net-(OK4-EMIT)") (class "Default")
      (node (ref "OK4") (pin "3") (pinfunction "EMIT_3") (pintype "passive"))
      (node (ref "R15") (pin "1") (pinfunction "1_1") (pintype "passive"))
    )
    (net (code "50") (name "Net-(OK5-A)") (class "Default")
      (node (ref "OK5") (pin "1") (pinfunction "A_1") (pintype "passive"))
      (node (ref "R19") (pin "1") (pinfunction "1_1") (pintype "passive"))
    )
    (net (code "51") (name "Net-(OK5-C)") (class "Default")
      (node (ref "LED5") (pin "A") (pinfunction "A_A") (pintype "passive"))
      (node (ref "OK5") (pin "2") (pinfunction "C_2") (pintype "passive"))
    )
    (net (code "52") (name "Net-(OK5-EMIT)") (class "Default")
      (node (ref "OK5") (pin "3") (pinfunction "EMIT_3") (pintype "passive"))
      (node (ref "R18") (pin "1") (pinfunction "1_1") (pintype "passive"))
    )
    (net (code "53") (name "Net-(OK6-A)") (class "Default")
      (node (ref "OK6") (pin "1") (pinfunction "A_1") (pintype "passive"))
      (node (ref "R22") (pin "1") (pinfunction "1_1") (pintype "passive"))
    )
    (net (code "54") (name "Net-(OK6-C)") (class "Default")
      (node (ref "LED6") (pin "A") (pinfunction "A_A") (pintype "passive"))
      (node (ref "OK6") (pin "2") (pinfunction "C_2") (pintype "passive"))
    )
    (net (code "55") (name "Net-(OK6-EMIT)") (class "Default")
      (node (ref "OK6") (pin "3") (pinfunction "EMIT_3") (pintype "passive"))
      (node (ref "R21") (pin "1") (pinfunction "1_1") (pintype "passive"))
    )
    (net (code "56") (name "Net-(PWR-LED-PadC)") (class "Default")
      (node (ref "PWR-LED") (pin "C") (pinfunction "C_C") (pintype "passive"))
      (node (ref "R1") (pin "2") (pinfunction "2_2") (pintype "passive"))
    )
    (net (code "57") (name "Net-(Q1-B)") (class "Default")
      (node (ref "Q1") (pin "1") (pinfunction "B_1") (pintype "passive"))
      (node (ref "R5") (pin "2") (pinfunction "2_2") (pintype "passive"))
    )
    (net (code "58") (name "Net-(Q1-C)") (class "Default")
      (node (ref "D2") (pin "A") (pinfunction "A_A") (pintype "passive"))
      (node (ref "K1") (pin "A2") (pinfunction "A2_A2") (pintype "passive"))
      (node (ref "Q1") (pin "3") (pinfunction "C_3") (pintype "passive"))
    )
    (net (code "59") (name "Net-(Q2-B)") (class "Default")
      (node (ref "Q2") (pin "1") (pinfunction "B_1") (pintype "passive"))
      (node (ref "R9") (pin "2") (pinfunction "2_2") (pintype "passive"))
    )
    (net (code "60") (name "Net-(Q2-C)") (class "Default")
      (node (ref "D4") (pin "A") (pinfunction "A_A") (pintype "passive"))
      (node (ref "K2") (pin "A2") (pinfunction "A2_A2") (pintype "passive"))
      (node (ref "Q2") (pin "3") (pinfunction "C_3") (pintype "passive"))
    )
    (net (code "61") (name "Net-(Q3-B)") (class "Default")
      (node (ref "Q3") (pin "1") (pinfunction "B_1") (pintype "passive"))
      (node (ref "R12") (pin "2") (pinfunction "2_2") (pintype "passive"))
    )
    (net (code "62") (name "Net-(Q3-C)") (class "Default")
      (node (ref "D6") (pin "A") (pinfunction "A_A") (pintype "passive"))
      (node (ref "K3") (pin "A2") (pinfunction "A2_A2") (pintype "passive"))
      (node (ref "Q3") (pin "3") (pinfunction "C_3") (pintype "passive"))
    )
    (net (code "63") (name "Net-(Q4-B)") (class "Default")
      (node (ref "Q4") (pin "1") (pinfunction "B_1") (pintype "passive"))
      (node (ref "R15") (pin "2") (pinfunction "2_2") (pintype "passive"))
    )
    (net (code "64") (name "Net-(Q4-C)") (class "Default")
      (node (ref "D8") (pin "A") (pinfunction "A_A") (pintype "passive"))
      (node (ref "K4") (pin "A2") (pinfunction "A2_A2") (pintype "passive"))
      (node (ref "Q4") (pin "3") (pinfunction "C_3") (pintype "passive"))
    )
    (net (code "65") (name "Net-(Q5-B)") (class "Default")
      (node (ref "Q5") (pin "1") (pinfunction "B_1") (pintype "passive"))
      (node (ref "R18") (pin "2") (pinfunction "2_2") (pintype "passive"))
    )
    (net (code "66") (name "Net-(Q5-C)") (class "Default")
      (node (ref "D10") (pin "A") (pinfunction "A_A") (pintype "passive"))
      (node (ref "K5") (pin "A2") (pinfunction "A2_A2") (pintype "passive"))
      (node (ref "Q5") (pin "3") (pinfunction "C_3") (pintype "passive"))
    )
    (net (code "67") (name "Net-(Q6-B)") (class "Default")
      (node (ref "Q6") (pin "1") (pinfunction "B_1") (pintype "passive"))
      (node (ref "R21") (pin "2") (pinfunction "2_2") (pintype "passive"))
    )
    (net (code "68") (name "Net-(Q6-C)") (class "Default")
      (node (ref "D12") (pin "A") (pinfunction "A_A") (pintype "passive"))
      (node (ref "K6") (pin "A2") (pinfunction "A2_A2") (pintype "passive"))
      (node (ref "Q6") (pin "3") (pinfunction "C_3") (pintype "passive"))
    )
    (net (code "69") (name "VCC") (class "Default")
      (node (ref "5V-INP") (pin "1") (pinfunction "1_1") (pintype "passive"))
      (node (ref "5V-SUPPLY") (pin "1") (pinfunction "1_1") (pintype "passive"))
      (node (ref "5V-SUPPLY") (pin "2") (pinfunction "1_2") (pintype "passive"))
      (node (ref "5V-SUPPLY") (pin "3") (pinfunction "1_3") (pintype "passive"))
      (node (ref "5V-SUPPLY") (pin "4") (pinfunction "1_4") (pintype "passive"))
      (node (ref "5V-SUPPLY") (pin "5") (pinfunction "1_5") (pintype "passive"))
      (node (ref "5V-SUPPLY") (pin "6") (pinfunction "1_6") (pintype "passive"))
      (node (ref "C1") (pin "1") (pinfunction "+_1") (pintype "passive"))
      (node (ref "CHIP-REGULATOR") (pin "2") (pinfunction "VO_2") (pintype "passive"))
      (node (ref "DEBUG") (pin "1") (pinfunction "1_1") (pintype "passive"))
      (node (ref "IC1") (pin "27") (pinfunction "AVCC_27") (pintype "power_in"))
      (node (ref "IC1") (pin "29") (pinfunction "AREF_29") (pintype "passive"))
      (node (ref "ISP-HEADER") (pin "2") (pinfunction "2_2") (pintype "passive"))
      (node (ref "LCD1") (pin "15") (pinfunction "A_15") (pintype "power_in"))
      (node (ref "LCD1") (pin "2") (pinfunction "VDD_2") (pintype "power_in"))
      (node (ref "PWR-LED") (pin "A") (pinfunction "A_A") (pintype "passive"))
      (node (ref "R2") (pin "1") (pinfunction "1_1") (pintype "passive"))
      (node (ref "R3") (pin "E") (pinfunction "E_E") (pintype "passive"))
    )
    (net (code "70") (name "unconnected-(DEBUG-Pad5)") (class "Default")
      (node (ref "DEBUG") (pin "5") (pinfunction "5_5") (pintype "passive"))
    )
    (net (code "71") (name "unconnected-(DEBUG-Pad6)") (class "Default")
      (node (ref "DEBUG") (pin "6") (pinfunction "6_6") (pintype "passive"))
    )
    (net (code "72") (name "unconnected-(IC1A-(ADC4)PA4-Pad33)") (class "Default")
      (node (ref "IC1") (pin "33") (pinfunction "(ADC4)PA4_33") (pintype "bidirectional"))
    )
    (net (code "73") (name "unconnected-(IC1A-(ADC5)PA5-Pad32)") (class "Default")
      (node (ref "IC1") (pin "32") (pinfunction "(ADC5)PA5_32") (pintype "bidirectional"))
    )
    (net (code "74") (name "unconnected-(IC1A-(ADC6)PA6-Pad31)") (class "Default")
      (node (ref "IC1") (pin "31") (pinfunction "(ADC6)PA6_31") (pintype "bidirectional"))
    )
    (net (code "75") (name "unconnected-(IC1A-(ADC7)PA7-Pad30)") (class "Default")
      (node (ref "IC1") (pin "30") (pinfunction "(ADC7)PA7_30") (pintype "bidirectional"))
    )
    (net (code "76") (name "unconnected-(IC1A-(INT2{slash}AIN0)PB2-Pad42)") (class "Default")
      (node (ref "IC1") (pin "42") (pinfunction "(INT2/AIN0)PB2_42") (pintype "bidirectional"))
    )
    (net (code "77") (name "unconnected-(IC1A-(OC0{slash}AIN1)PB3-Pad43)") (class "Default")
      (node (ref "IC1") (pin "43") (pinfunction "(OC0/AIN1)PB3_43") (pintype "bidirectional"))
    )
    (net (code "78") (name "unconnected-(IC1A-(TOSC1)PC6-Pad25)") (class "Default")
      (node (ref "IC1") (pin "25") (pinfunction "(TOSC1)PC6_25") (pintype "bidirectional"))
    )
    (net (code "79") (name "unconnected-(IC1A-(TOSC2)PC7-Pad26)") (class "Default")
      (node (ref "IC1") (pin "26") (pinfunction "(TOSC2)PC7_26") (pintype "bidirectional"))
    )
    (net (code "80") (name "unconnected-(IC1A-(~{SS})PB4-Pad44)") (class "Default")
      (node (ref "IC1") (pin "44") (pinfunction "(~{SS})PB4_44") (pintype "bidirectional"))
    )
    (net (code "81") (name "unconnected-(IC1A-XTAL1-Pad8)") (class "Default")
      (node (ref "IC1") (pin "8") (pinfunction "XTAL1_8") (pintype "bidirectional"))
    )
    (net (code "82") (name "unconnected-(IC1A-XTAL2-Pad7)") (class "Default")
      (node (ref "IC1") (pin "7") (pinfunction "XTAL2_7") (pintype "bidirectional"))
    )
    (net (code "83") (name "unconnected-(J1-PadGNDBREAK)") (class "Default")
      (node (ref "J1") (pin "GNDBREAK") (pinfunction "GNDBREAK_GNDBREAK") (pintype "bidirectional"))
    )
    (net (code "84") (name "unconnected-(K1-PadNC)") (class "Default")
      (node (ref "K1") (pin "NC") (pinfunction "NC_NC") (pintype "passive"))
    )
    (net (code "85") (name "unconnected-(K2-PadNC)") (class "Default")
      (node (ref "K2") (pin "NC") (pinfunction "NC_NC") (pintype "passive"))
    )
    (net (code "86") (name "unconnected-(K3-PadNC)") (class "Default")
      (node (ref "K3") (pin "NC") (pinfunction "NC_NC") (pintype "passive"))
    )
    (net (code "87") (name "unconnected-(K4-PadNC)") (class "Default")
      (node (ref "K4") (pin "NC") (pinfunction "NC_NC") (pintype "passive"))
    )
    (net (code "88") (name "unconnected-(K5-PadNC)") (class "Default")
      (node (ref "K5") (pin "NC") (pinfunction "NC_NC") (pintype "passive"))
    )
    (net (code "89") (name "unconnected-(K6-PadNC)") (class "Default")
      (node (ref "K6") (pin "NC") (pinfunction "NC_NC") (pintype "passive"))
    )
  )
)
